# ParametricEQ_V_1_0.net
KiCad netlist of a schematic drawn in EAGLE
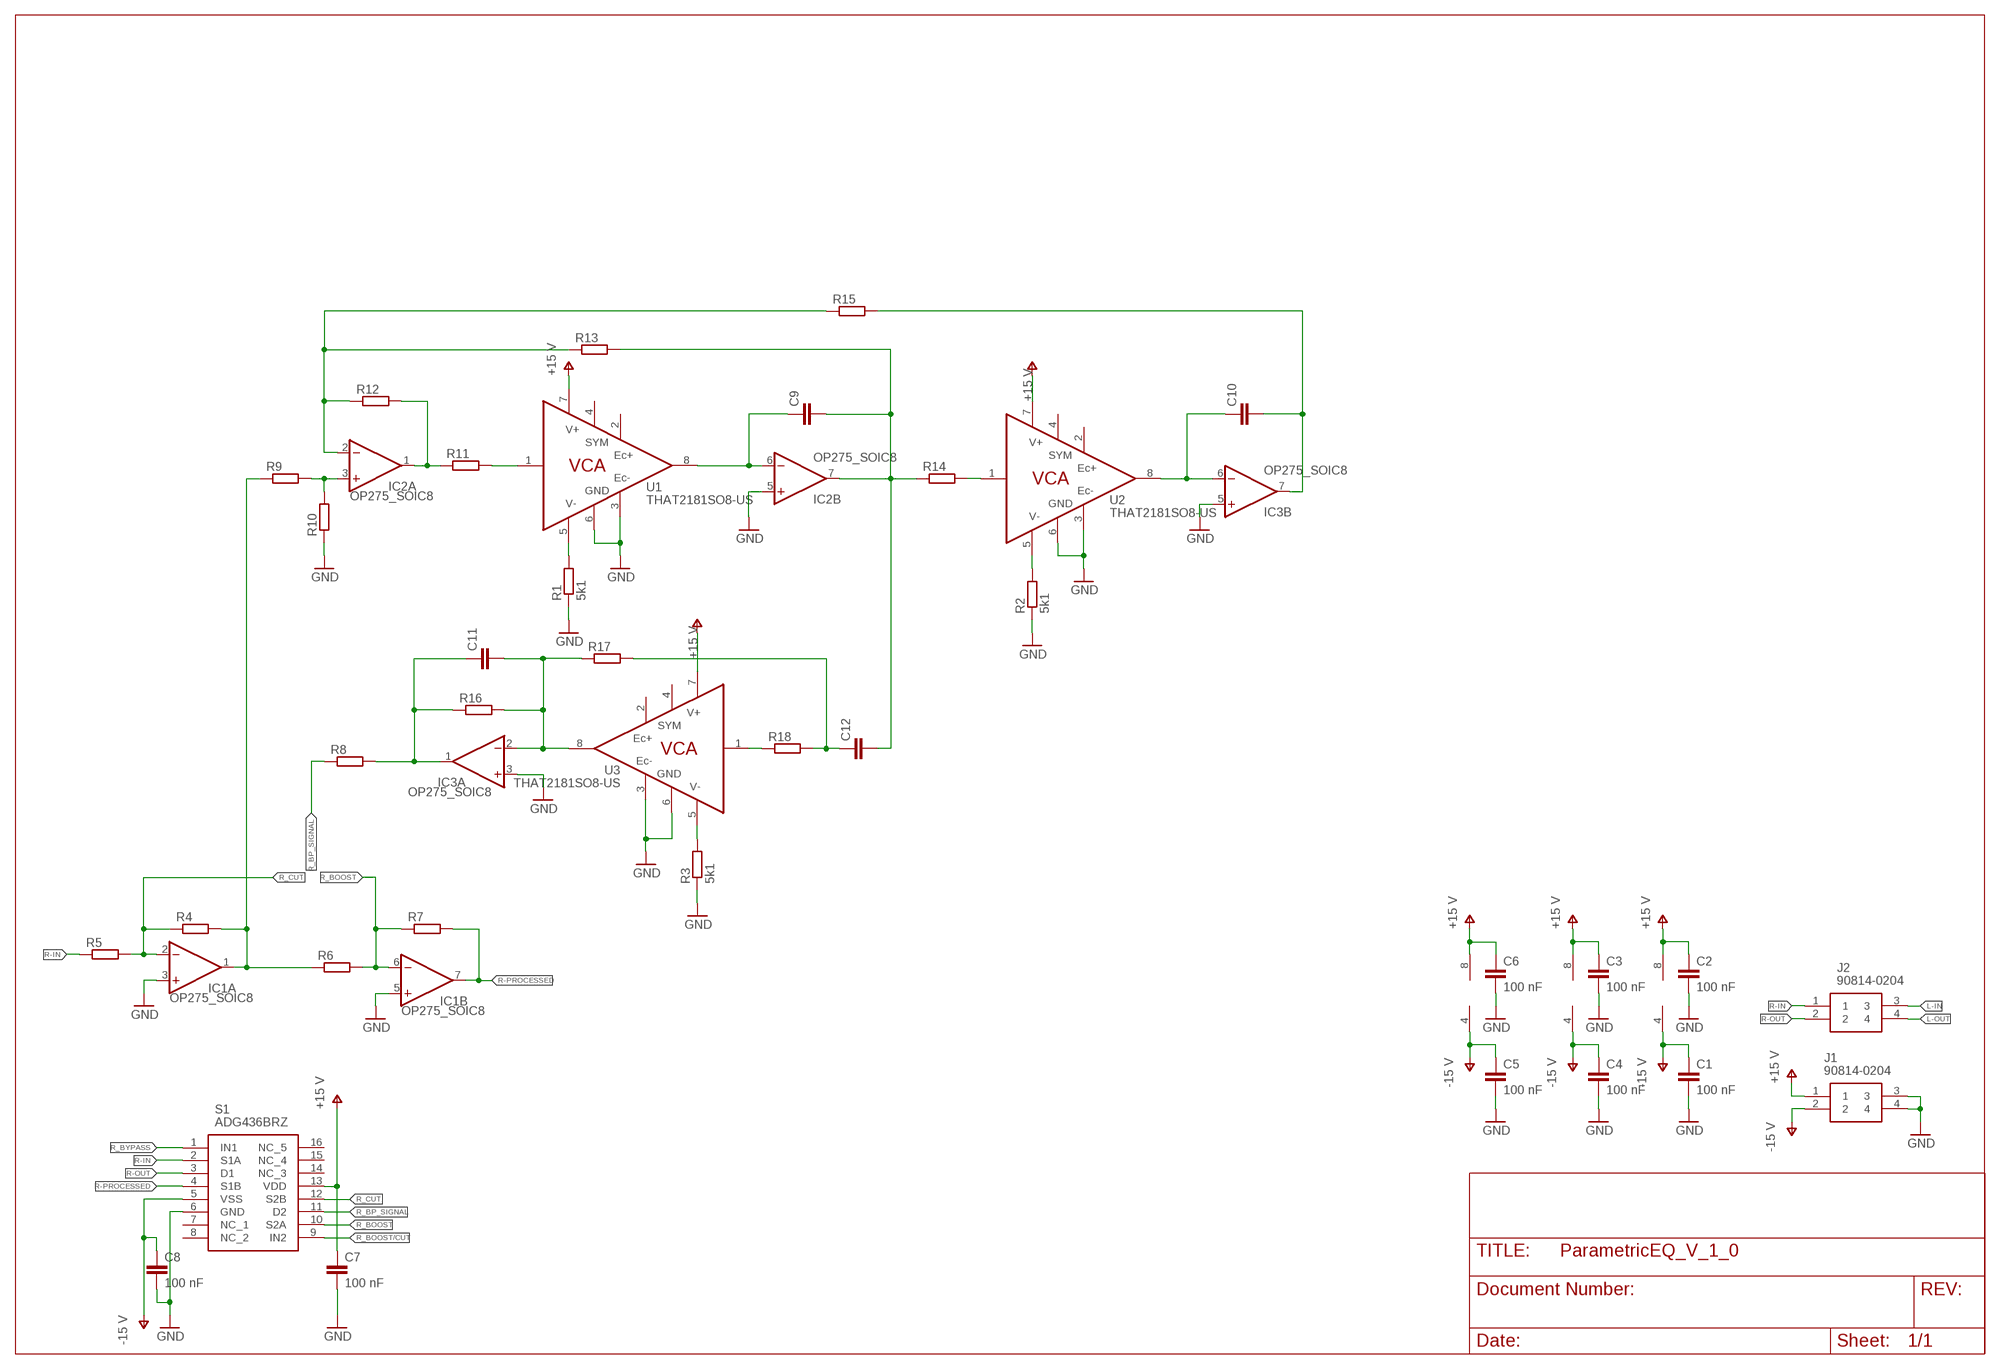
[diagram p0: schematic, sheet 1]

(export (version "E")
  (design (tool "Eeschema 10.0.6"))
  (components
    (comp (ref "C1")
      (value "100 nF")
      (footprint "eagle-import:C0603")
      (libsource (lib "eagle-import") (part "CAPACITOR_0603"))
    )
    (comp (ref "C2")
      (value "100 nF")
      (footprint "eagle-import:C0603")
      (libsource (lib "eagle-import") (part "CAPACITOR_0603"))
    )
    (comp (ref "C3")
      (value "100 nF")
      (footprint "eagle-import:C0603")
      (libsource (lib "eagle-import") (part "CAPACITOR_0603"))
    )
    (comp (ref "C4")
      (value "100 nF")
      (footprint "eagle-import:C0603")
      (libsource (lib "eagle-import") (part "CAPACITOR_0603"))
    )
    (comp (ref "C5")
      (value "100 nF")
      (footprint "eagle-import:C0603")
      (libsource (lib "eagle-import") (part "CAPACITOR_0603"))
    )
    (comp (ref "C6")
      (value "100 nF")
      (footprint "eagle-import:C0603")
      (libsource (lib "eagle-import") (part "CAPACITOR_0603"))
    )
    (comp (ref "C7")
      (value "100 nF")
      (footprint "eagle-import:C0603")
      (libsource (lib "eagle-import") (part "CAPACITOR_0603"))
    )
    (comp (ref "C8")
      (value "100 nF")
      (footprint "eagle-import:C0603")
      (libsource (lib "eagle-import") (part "CAPACITOR_0603"))
    )
    (comp (ref "C9")
      (value "CAPACITOR_0603")
      (footprint "eagle-import:C0603")
      (libsource (lib "eagle-import") (part "CAPACITOR_0603"))
    )
    (comp (ref "C10")
      (value "CAPACITOR_0603")
      (footprint "eagle-import:C0603")
      (libsource (lib "eagle-import") (part "CAPACITOR_0603"))
    )
    (comp (ref "C11")
      (value "CAPACITOR_0603")
      (footprint "eagle-import:C0603")
      (libsource (lib "eagle-import") (part "CAPACITOR_0603"))
    )
    (comp (ref "C12")
      (value "CAPACITOR_0603")
      (footprint "eagle-import:C0603")
      (libsource (lib "eagle-import") (part "CAPACITOR_0603"))
    )
    (comp (ref "IC1")
      (value "OP275_SOIC8")
      (footprint "eagle-import:SOIC8")
      (fields (field (name "MOUSER_PART_NUMBER") "584-OP275GSZ-R7"))
      (libsource (lib "eagle-import") (part "OP275_SOIC8"))
    )
    (comp (ref "IC2")
      (value "OP275_SOIC8")
      (footprint "eagle-import:SOIC8")
      (fields (field (name "MOUSER_PART_NUMBER") "584-OP275GSZ-R7"))
      (libsource (lib "eagle-import") (part "OP275_SOIC8"))
    )
    (comp (ref "IC3")
      (value "OP275_SOIC8")
      (footprint "eagle-import:SOIC8")
      (fields (field (name "MOUSER_PART_NUMBER") "584-OP275GSZ-R7"))
      (libsource (lib "eagle-import") (part "OP275_SOIC8"))
    )
    (comp (ref "J1")
      (value "90814-0204")
      (footprint "eagle-import:MOLEX_90814-0204")
      (fields (field (name "MOUSER_PART_NUMBER") "538-90814-0204"))
      (libsource (lib "eagle-import") (part "90814-0204"))
    )
    (comp (ref "J2")
      (value "90814-0204")
      (footprint "eagle-import:MOLEX_90814-0204")
      (fields (field (name "MOUSER_PART_NUMBER") "538-90814-0204"))
      (libsource (lib "eagle-import") (part "90814-0204"))
    )
    (comp (ref "R1")
      (value "5k1")
      (footprint "eagle-import:R0603")
      (libsource (lib "eagle-import") (part "RESISTOR_0603"))
    )
    (comp (ref "R2")
      (value "5k1")
      (footprint "eagle-import:R0603")
      (libsource (lib "eagle-import") (part "RESISTOR_0603"))
    )
    (comp (ref "R3")
      (value "5k1")
      (footprint "eagle-import:R0603")
      (libsource (lib "eagle-import") (part "RESISTOR_0603"))
    )
    (comp (ref "R4")
      (value "RESISTOR_0603")
      (footprint "eagle-import:R0603")
      (libsource (lib "eagle-import") (part "RESISTOR_0603"))
    )
    (comp (ref "R5")
      (value "RESISTOR_0603")
      (footprint "eagle-import:R0603")
      (libsource (lib "eagle-import") (part "RESISTOR_0603"))
    )
    (comp (ref "R6")
      (value "RESISTOR_0603")
      (footprint "eagle-import:R0603")
      (libsource (lib "eagle-import") (part "RESISTOR_0603"))
    )
    (comp (ref "R7")
      (value "RESISTOR_0603")
      (footprint "eagle-import:R0603")
      (libsource (lib "eagle-import") (part "RESISTOR_0603"))
    )
    (comp (ref "R8")
      (value "RESISTOR_0603")
      (footprint "eagle-import:R0603")
      (libsource (lib "eagle-import") (part "RESISTOR_0603"))
    )
    (comp (ref "R9")
      (value "RESISTOR_0603")
      (footprint "eagle-import:R0603")
      (libsource (lib "eagle-import") (part "RESISTOR_0603"))
    )
    (comp (ref "R10")
      (value "RESISTOR_0603")
      (footprint "eagle-import:R0603")
      (libsource (lib "eagle-import") (part "RESISTOR_0603"))
    )
    (comp (ref "R11")
      (value "RESISTOR_0603")
      (footprint "eagle-import:R0603")
      (libsource (lib "eagle-import") (part "RESISTOR_0603"))
    )
    (comp (ref "R12")
      (value "RESISTOR_0603")
      (footprint "eagle-import:R0603")
      (libsource (lib "eagle-import") (part "RESISTOR_0603"))
    )
    (comp (ref "R13")
      (value "RESISTOR_0603")
      (footprint "eagle-import:R0603")
      (libsource (lib "eagle-import") (part "RESISTOR_0603"))
    )
    (comp (ref "R14")
      (value "RESISTOR_0603")
      (footprint "eagle-import:R0603")
      (libsource (lib "eagle-import") (part "RESISTOR_0603"))
    )
    (comp (ref "R15")
      (value "RESISTOR_0603")
      (footprint "eagle-import:R0603")
      (libsource (lib "eagle-import") (part "RESISTOR_0603"))
    )
    (comp (ref "R16")
      (value "RESISTOR_0603")
      (footprint "eagle-import:R0603")
      (libsource (lib "eagle-import") (part "RESISTOR_0603"))
    )
    (comp (ref "R17")
      (value "RESISTOR_0603")
      (footprint "eagle-import:R0603")
      (libsource (lib "eagle-import") (part "RESISTOR_0603"))
    )
    (comp (ref "R18")
      (value "RESISTOR_0603")
      (footprint "eagle-import:R0603")
      (libsource (lib "eagle-import") (part "RESISTOR_0603"))
    )
    (comp (ref "S1")
      (value "ADG436BRZ")
      (footprint "eagle-import:SOIC127P600X175-16N")
      (fields (field (name "MOUSER_PART_NUMBER") "584-ADG436BRZ"))
      (libsource (lib "eagle-import") (part "ADG436BRZ"))
    )
    (comp (ref "U1")
      (value "THAT2181SO8-US")
      (footprint "eagle-import:SO08")
      (fields (field (name "MOUSER_PART_NUMBER") "887-2181CS08-U"))
      (libsource (lib "eagle-import") (part "THAT2181SSO8-U"))
    )
    (comp (ref "U2")
      (value "THAT2181SO8-US")
      (footprint "eagle-import:SO08")
      (fields (field (name "MOUSER_PART_NUMBER") "887-2181CS08-U"))
      (libsource (lib "eagle-import") (part "THAT2181SSO8-U"))
    )
    (comp (ref "U3")
      (value "THAT2181SO8-US")
      (footprint "eagle-import:SO08")
      (fields (field (name "MOUSER_PART_NUMBER") "887-2181CS08-U"))
      (libsource (lib "eagle-import") (part "THAT2181SSO8-U"))
    )
  )
  (nets
    (net (code "1") (name "+15 V") (class "Default")
      (node (ref "C2") (pin "1") (pinfunction "1_1") (pintype "passive"))
      (node (ref "C3") (pin "1") (pinfunction "1_1") (pintype "passive"))
      (node (ref "C6") (pin "1") (pinfunction "1_1") (pintype "passive"))
      (node (ref "C7") (pin "1") (pinfunction "1_1") (pintype "passive"))
      (node (ref "IC1") (pin "8") (pinfunction "V+_8") (pintype "power_in"))
      (node (ref "IC2") (pin "8") (pinfunction "V+_8") (pintype "power_in"))
      (node (ref "IC3") (pin "8") (pinfunction "V+_8") (pintype "power_in"))
      (node (ref "J1") (pin "1") (pinfunction "1_1") (pintype "bidirectional"))
      (node (ref "S1") (pin "13") (pinfunction "VDD_13") (pintype "bidirectional"))
      (node (ref "U1") (pin "7") (pinfunction "V+_7") (pintype "power_in"))
      (node (ref "U2") (pin "7") (pinfunction "V+_7") (pintype "power_in"))
      (node (ref "U3") (pin "7") (pinfunction "V+_7") (pintype "power_in"))
    )
    (net (code "2") (name "-15 V") (class "Default")
      (node (ref "C1") (pin "1") (pinfunction "1_1") (pintype "passive"))
      (node (ref "C4") (pin "1") (pinfunction "1_1") (pintype "passive"))
      (node (ref "C5") (pin "1") (pinfunction "1_1") (pintype "passive"))
      (node (ref "C8") (pin "1") (pinfunction "1_1") (pintype "passive"))
      (node (ref "IC1") (pin "4") (pinfunction "V-_4") (pintype "power_in"))
      (node (ref "IC2") (pin "4") (pinfunction "V-_4") (pintype "power_in"))
      (node (ref "IC3") (pin "4") (pinfunction "V-_4") (pintype "power_in"))
      (node (ref "J1") (pin "2") (pinfunction "2_2") (pintype "bidirectional"))
      (node (ref "S1") (pin "5") (pinfunction "VSS_5") (pintype "bidirectional"))
    )
    (net (code "3") (name "GND") (class "Default")
      (node (ref "C1") (pin "2") (pinfunction "2_2") (pintype "passive"))
      (node (ref "C2") (pin "2") (pinfunction "2_2") (pintype "passive"))
      (node (ref "C3") (pin "2") (pinfunction "2_2") (pintype "passive"))
      (node (ref "C4") (pin "2") (pinfunction "2_2") (pintype "passive"))
      (node (ref "C5") (pin "2") (pinfunction "2_2") (pintype "passive"))
      (node (ref "C6") (pin "2") (pinfunction "2_2") (pintype "passive"))
      (node (ref "C7") (pin "2") (pinfunction "2_2") (pintype "passive"))
      (node (ref "C8") (pin "2") (pinfunction "2_2") (pintype "passive"))
      (node (ref "IC1") (pin "3") (pinfunction "+IN_3") (pintype "input"))
      (node (ref "IC1") (pin "5") (pinfunction "+IN_5") (pintype "input"))
      (node (ref "IC2") (pin "5") (pinfunction "+IN_5") (pintype "input"))
      (node (ref "IC3") (pin "3") (pinfunction "+IN_3") (pintype "input"))
      (node (ref "IC3") (pin "5") (pinfunction "+IN_5") (pintype "input"))
      (node (ref "J1") (pin "3") (pinfunction "3_3") (pintype "bidirectional"))
      (node (ref "J1") (pin "4") (pinfunction "4_4") (pintype "bidirectional"))
      (node (ref "R1") (pin "1") (pinfunction "1_1") (pintype "passive"))
      (node (ref "R10") (pin "1") (pinfunction "1_1") (pintype "passive"))
      (node (ref "R2") (pin "1") (pinfunction "1_1") (pintype "passive"))
      (node (ref "R3") (pin "1") (pinfunction "1_1") (pintype "passive"))
      (node (ref "S1") (pin "6") (pinfunction "GND_6") (pintype "bidirectional"))
      (node (ref "U1") (pin "3") (pinfunction "EC-_3") (pintype "output"))
      (node (ref "U1") (pin "6") (pinfunction "GND_6") (pintype "passive"))
      (node (ref "U2") (pin "3") (pinfunction "EC-_3") (pintype "output"))
      (node (ref "U2") (pin "6") (pinfunction "GND_6") (pintype "passive"))
      (node (ref "U3") (pin "3") (pinfunction "EC-_3") (pintype "output"))
      (node (ref "U3") (pin "6") (pinfunction "GND_6") (pintype "passive"))
    )
    (net (code "4") (name "L-IN") (class "Default")
      (node (ref "J2") (pin "3") (pinfunction "3_3") (pintype "bidirectional"))
    )
    (net (code "5") (name "L-OUT") (class "Default")
      (node (ref "J2") (pin "4") (pinfunction "4_4") (pintype "bidirectional"))
    )
    (net (code "6") (name "Net-(C12-Pad1)") (class "Default")
      (node (ref "C12") (pin "1") (pinfunction "1_1") (pintype "passive"))
      (node (ref "R17") (pin "2") (pinfunction "2_2") (pintype "passive"))
      (node (ref "R18") (pin "2") (pinfunction "2_2") (pintype "passive"))
    )
    (net (code "7") (name "Net-(IC1A-OUT)") (class "Default")
      (node (ref "IC1") (pin "1") (pinfunction "OUT_1") (pintype "output"))
      (node (ref "R4") (pin "2") (pinfunction "2_2") (pintype "passive"))
      (node (ref "R6") (pin "1") (pinfunction "1_1") (pintype "passive"))
      (node (ref "R9") (pin "1") (pinfunction "1_1") (pintype "passive"))
    )
    (net (code "8") (name "Net-(IC2A-+IN)") (class "Default")
      (node (ref "IC2") (pin "3") (pinfunction "+IN_3") (pintype "input"))
      (node (ref "R10") (pin "2") (pinfunction "2_2") (pintype "passive"))
      (node (ref "R9") (pin "2") (pinfunction "2_2") (pintype "passive"))
    )
    (net (code "9") (name "Net-(IC2A--IN)") (class "Default")
      (node (ref "IC2") (pin "2") (pinfunction "-IN_2") (pintype "input"))
      (node (ref "R12") (pin "1") (pinfunction "1_1") (pintype "passive"))
      (node (ref "R13") (pin "1") (pinfunction "1_1") (pintype "passive"))
      (node (ref "R15") (pin "1") (pinfunction "1_1") (pintype "passive"))
    )
    (net (code "10") (name "Net-(IC2A-OUT)") (class "Default")
      (node (ref "IC2") (pin "1") (pinfunction "OUT_1") (pintype "output"))
      (node (ref "R11") (pin "1") (pinfunction "1_1") (pintype "passive"))
      (node (ref "R12") (pin "2") (pinfunction "2_2") (pintype "passive"))
    )
    (net (code "11") (name "Net-(IC2B--IN)") (class "Default")
      (node (ref "C9") (pin "1") (pinfunction "1_1") (pintype "passive"))
      (node (ref "IC2") (pin "6") (pinfunction "-IN_6") (pintype "input"))
      (node (ref "U1") (pin "8") (pinfunction "OUT_8") (pintype "output"))
    )
    (net (code "12") (name "Net-(IC2B-OUT)") (class "Default")
      (node (ref "C12") (pin "2") (pinfunction "2_2") (pintype "passive"))
      (node (ref "C9") (pin "2") (pinfunction "2_2") (pintype "passive"))
      (node (ref "IC2") (pin "7") (pinfunction "OUT_7") (pintype "output"))
      (node (ref "R13") (pin "2") (pinfunction "2_2") (pintype "passive"))
      (node (ref "R14") (pin "1") (pinfunction "1_1") (pintype "passive"))
    )
    (net (code "13") (name "Net-(IC3A--IN)") (class "Default")
      (node (ref "C11") (pin "2") (pinfunction "2_2") (pintype "passive"))
      (node (ref "IC3") (pin "2") (pinfunction "-IN_2") (pintype "input"))
      (node (ref "R16") (pin "2") (pinfunction "2_2") (pintype "passive"))
      (node (ref "R17") (pin "1") (pinfunction "1_1") (pintype "passive"))
      (node (ref "U3") (pin "8") (pinfunction "OUT_8") (pintype "output"))
    )
    (net (code "14") (name "Net-(IC3A-OUT)") (class "Default")
      (node (ref "C11") (pin "1") (pinfunction "1_1") (pintype "passive"))
      (node (ref "IC3") (pin "1") (pinfunction "OUT_1") (pintype "output"))
      (node (ref "R16") (pin "1") (pinfunction "1_1") (pintype "passive"))
      (node (ref "R8") (pin "2") (pinfunction "2_2") (pintype "passive"))
    )
    (net (code "15") (name "Net-(IC3B--IN)") (class "Default")
      (node (ref "C10") (pin "1") (pinfunction "1_1") (pintype "passive"))
      (node (ref "IC3") (pin "6") (pinfunction "-IN_6") (pintype "input"))
      (node (ref "U2") (pin "8") (pinfunction "OUT_8") (pintype "output"))
    )
    (net (code "16") (name "Net-(IC3B-OUT)") (class "Default")
      (node (ref "C10") (pin "2") (pinfunction "2_2") (pintype "passive"))
      (node (ref "IC3") (pin "7") (pinfunction "OUT_7") (pintype "output"))
      (node (ref "R15") (pin "2") (pinfunction "2_2") (pintype "passive"))
    )
    (net (code "17") (name "Net-(U1-IN)") (class "Default")
      (node (ref "R11") (pin "2") (pinfunction "2_2") (pintype "passive"))
      (node (ref "U1") (pin "1") (pinfunction "IN_1") (pintype "input"))
    )
    (net (code "18") (name "Net-(U1-V-)") (class "Default")
      (node (ref "R1") (pin "2") (pinfunction "2_2") (pintype "passive"))
      (node (ref "U1") (pin "5") (pinfunction "V-_5") (pintype "power_in"))
    )
    (net (code "19") (name "Net-(U2-IN)") (class "Default")
      (node (ref "R14") (pin "2") (pinfunction "2_2") (pintype "passive"))
      (node (ref "U2") (pin "1") (pinfunction "IN_1") (pintype "input"))
    )
    (net (code "20") (name "Net-(U2-V-)") (class "Default")
      (node (ref "R2") (pin "2") (pinfunction "2_2") (pintype "passive"))
      (node (ref "U2") (pin "5") (pinfunction "V-_5") (pintype "power_in"))
    )
    (net (code "21") (name "Net-(U3-IN)") (class "Default")
      (node (ref "R18") (pin "1") (pinfunction "1_1") (pintype "passive"))
      (node (ref "U3") (pin "1") (pinfunction "IN_1") (pintype "input"))
    )
    (net (code "22") (name "Net-(U3-V-)") (class "Default")
      (node (ref "R3") (pin "2") (pinfunction "2_2") (pintype "passive"))
      (node (ref "U3") (pin "5") (pinfunction "V-_5") (pintype "power_in"))
    )
    (net (code "23") (name "R-IN") (class "Default")
      (node (ref "J2") (pin "1") (pinfunction "1_1") (pintype "bidirectional"))
      (node (ref "R5") (pin "1") (pinfunction "1_1") (pintype "passive"))
      (node (ref "S1") (pin "2") (pinfunction "S1A_2") (pintype "bidirectional"))
    )
    (net (code "24") (name "R-OUT") (class "Default")
      (node (ref "J2") (pin "2") (pinfunction "2_2") (pintype "bidirectional"))
      (node (ref "S1") (pin "3") (pinfunction "D1_3") (pintype "bidirectional"))
    )
    (net (code "25") (name "R-PROCESSED") (class "Default")
      (node (ref "IC1") (pin "7") (pinfunction "OUT_7") (pintype "output"))
      (node (ref "R7") (pin "2") (pinfunction "2_2") (pintype "passive"))
      (node (ref "S1") (pin "4") (pinfunction "S1B_4") (pintype "bidirectional"))
    )
    (net (code "26") (name "R_BOOST") (class "Default")
      (node (ref "IC1") (pin "6") (pinfunction "-IN_6") (pintype "input"))
      (node (ref "R6") (pin "2") (pinfunction "2_2") (pintype "passive"))
      (node (ref "R7") (pin "1") (pinfunction "1_1") (pintype "passive"))
      (node (ref "S1") (pin "10") (pinfunction "S2A_10") (pintype "bidirectional"))
    )
    (net (code "27") (name "R_BOOST{slash}CUT") (class "Default")
      (node (ref "S1") (pin "9") (pinfunction "IN2_9") (pintype "bidirectional"))
    )
    (net (code "28") (name "R_BP_SIGNAL") (class "Default")
      (node (ref "R8") (pin "1") (pinfunction "1_1") (pintype "passive"))
      (node (ref "S1") (pin "11") (pinfunction "D2_11") (pintype "bidirectional"))
    )
    (net (code "29") (name "R_BYPASS") (class "Default")
      (node (ref "S1") (pin "1") (pinfunction "IN1_1") (pintype "bidirectional"))
    )
    (net (code "30") (name "R_CUT") (class "Default")
      (node (ref "IC1") (pin "2") (pinfunction "-IN_2") (pintype "input"))
      (node (ref "R4") (pin "1") (pinfunction "1_1") (pintype "passive"))
      (node (ref "R5") (pin "2") (pinfunction "2_2") (pintype "passive"))
      (node (ref "S1") (pin "12") (pinfunction "S2B_12") (pintype "bidirectional"))
    )
    (net (code "31") (name "unconnected-(S1-NC_1-Pad7)") (class "Default")
      (node (ref "S1") (pin "7") (pinfunction "NC_1_7") (pintype "bidirectional"))
    )
    (net (code "32") (name "unconnected-(S1-NC_2-Pad8)") (class "Default")
      (node (ref "S1") (pin "8") (pinfunction "NC_2_8") (pintype "bidirectional"))
    )
    (net (code "33") (name "unconnected-(S1-NC_3-Pad14)") (class "Default")
      (node (ref "S1") (pin "14") (pinfunction "NC_3_14") (pintype "bidirectional"))
    )
    (net (code "34") (name "unconnected-(S1-NC_4-Pad15)") (class "Default")
      (node (ref "S1") (pin "15") (pinfunction "NC_4_15") (pintype "bidirectional"))
    )
    (net (code "35") (name "unconnected-(S1-NC_5-Pad16)") (class "Default")
      (node (ref "S1") (pin "16") (pinfunction "NC_5_16") (pintype "bidirectional"))
    )
    (net (code "36") (name "unconnected-(U1-EC+-Pad2)") (class "Default")
      (node (ref "U1") (pin "2") (pinfunction "EC+_2") (pintype "passive"))
    )
    (net (code "37") (name "unconnected-(U1-SYM-Pad4)") (class "Default")
      (node (ref "U1") (pin "4") (pinfunction "SYM_4") (pintype "passive"))
    )
    (net (code "38") (name "unconnected-(U2-EC+-Pad2)") (class "Default")
      (node (ref "U2") (pin "2") (pinfunction "EC+_2") (pintype "passive"))
    )
    (net (code "39") (name "unconnected-(U2-SYM-Pad4)") (class "Default")
      (node (ref "U2") (pin "4") (pinfunction "SYM_4") (pintype "passive"))
    )
    (net (code "40") (name "unconnected-(U3-EC+-Pad2)") (class "Default")
      (node (ref "U3") (pin "2") (pinfunction "EC+_2") (pintype "passive"))
    )
    (net (code "41") (name "unconnected-(U3-SYM-Pad4)") (class "Default")
      (node (ref "U3") (pin "4") (pinfunction "SYM_4") (pintype "passive"))
    )
  )
)
